# MAX2771-eval.net
KiCad netlist of a schematic drawn in Altium Designer
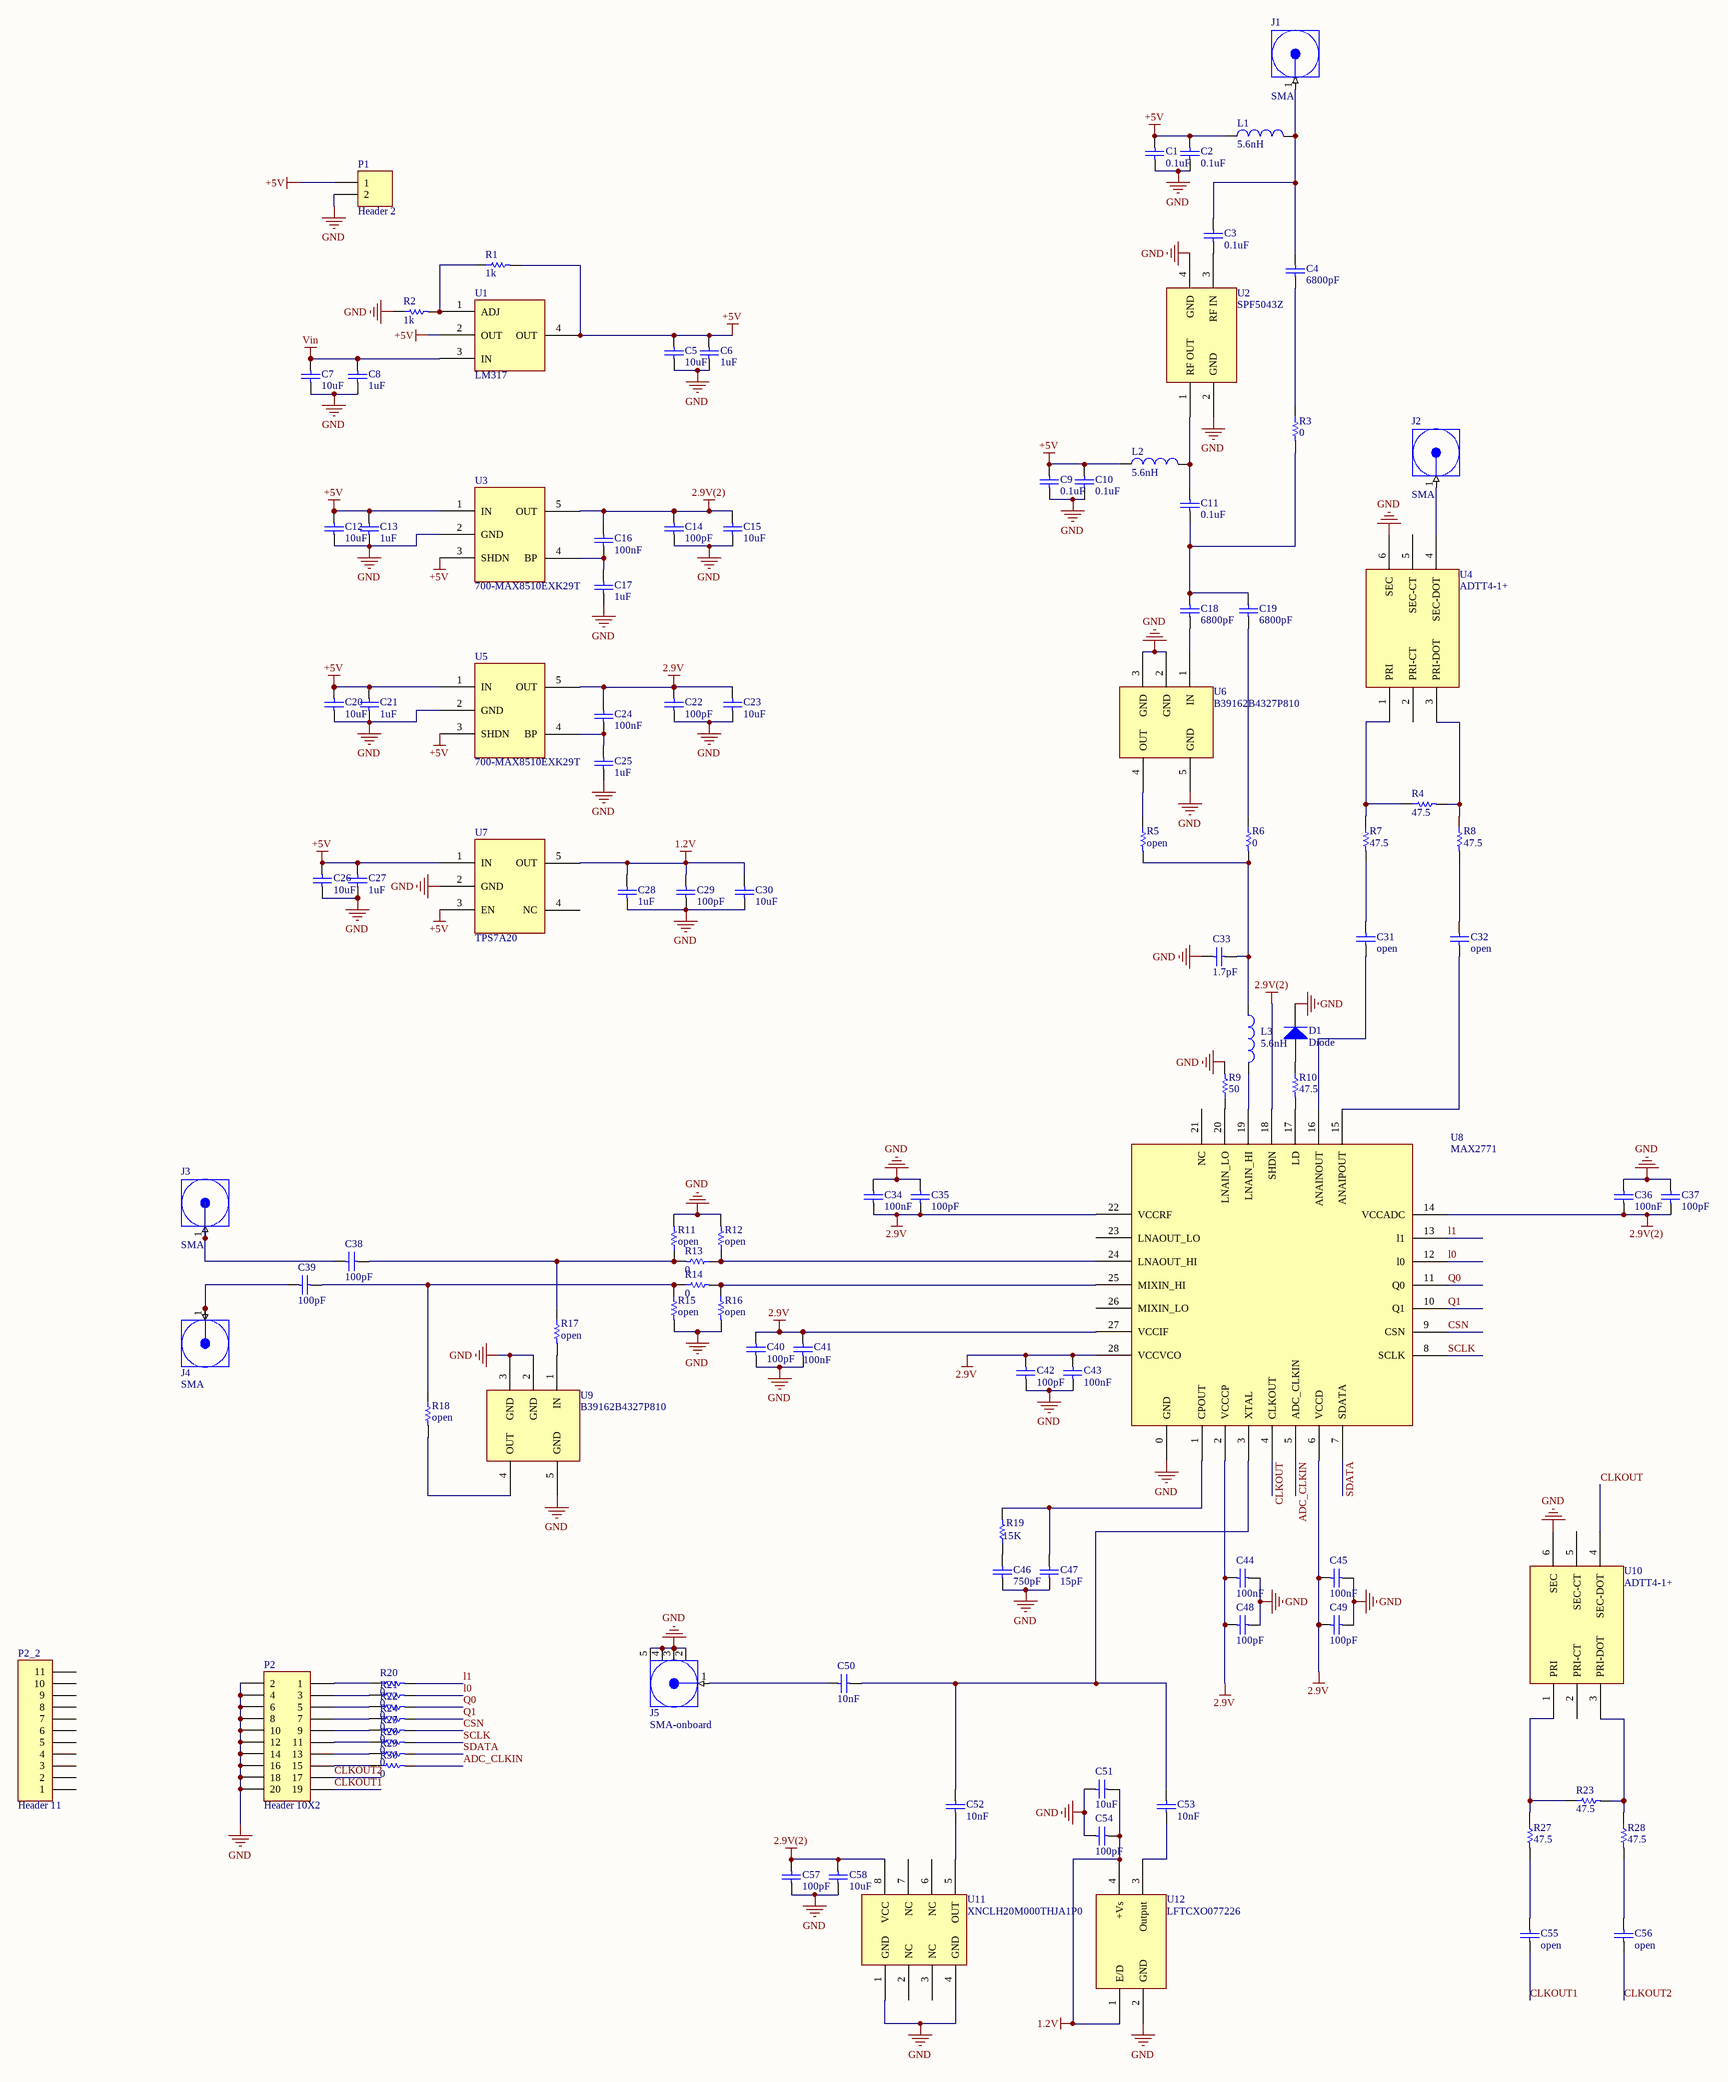
[diagram p0: MAX2771-eval.SchDoc]

(export (version "E")
  (design (tool "Eeschema 10.0.6"))
  (components
    (comp (ref "C1")
      (value "0.1uF")
      (footprint "0603")
      (description "Capacitor")
      (fields (field (name "Comment") "Cap") (field (name "PUBLISHER") "Altium Limited"))
      (libsource (lib "Miscellaneous Devices") (part "Cap"))
    )
    (comp (ref "C2")
      (value "0.1uF")
      (footprint "0603")
      (description "Capacitor")
      (fields (field (name "Comment") "Cap") (field (name "PUBLISHER") "Altium Limited"))
      (libsource (lib "Miscellaneous Devices") (part "Cap"))
    )
    (comp (ref "C3")
      (value "0.1uF")
      (footprint "0603")
      (description "Capacitor")
      (fields (field (name "Comment") "Cap") (field (name "PUBLISHER") "Altium Limited"))
      (libsource (lib "Miscellaneous Devices") (part "Cap"))
    )
    (comp (ref "C4")
      (value "6800pF")
      (footprint "0603")
      (description "Capacitor")
      (fields (field (name "Comment") "Cap") (field (name "PUBLISHER") "Altium Limited"))
      (libsource (lib "Miscellaneous Devices") (part "Cap"))
    )
    (comp (ref "C5")
      (value "10uF")
      (footprint "0603")
      (description "Capacitor")
      (fields (field (name "Comment") "Cap") (field (name "PUBLISHER") "Altium Limited"))
      (libsource (lib "Miscellaneous Devices") (part "Cap"))
    )
    (comp (ref "C6")
      (value "1uF")
      (footprint "0603")
      (description "Capacitor")
      (fields (field (name "Comment") "Cap") (field (name "PUBLISHER") "Altium Limited"))
      (libsource (lib "Miscellaneous Devices") (part "Cap"))
    )
    (comp (ref "C7")
      (value "10uF")
      (footprint "0603")
      (description "Capacitor")
      (fields (field (name "Comment") "Cap") (field (name "PUBLISHER") "Altium Limited"))
      (libsource (lib "Miscellaneous Devices") (part "Cap"))
    )
    (comp (ref "C8")
      (value "1uF")
      (footprint "0603")
      (description "Capacitor")
      (fields (field (name "Comment") "Cap") (field (name "PUBLISHER") "Altium Limited"))
      (libsource (lib "Miscellaneous Devices") (part "Cap"))
    )
    (comp (ref "C9")
      (value "0.1uF")
      (footprint "0603")
      (description "Capacitor")
      (fields (field (name "Comment") "Cap") (field (name "PUBLISHER") "Altium Limited"))
      (libsource (lib "Miscellaneous Devices") (part "Cap"))
    )
    (comp (ref "C10")
      (value "0.1uF")
      (footprint "0603")
      (description "Capacitor")
      (fields (field (name "Comment") "Cap") (field (name "PUBLISHER") "Altium Limited"))
      (libsource (lib "Miscellaneous Devices") (part "Cap"))
    )
    (comp (ref "C11")
      (value "0.1uF")
      (footprint "0603")
      (description "Capacitor")
      (fields (field (name "Comment") "Cap") (field (name "PUBLISHER") "Altium Limited"))
      (libsource (lib "Miscellaneous Devices") (part "Cap"))
    )
    (comp (ref "C12")
      (value "10uF")
      (footprint "0603")
      (description "Capacitor")
      (fields (field (name "Comment") "Cap") (field (name "PUBLISHER") "Altium Limited"))
      (libsource (lib "Miscellaneous Devices") (part "Cap"))
    )
    (comp (ref "C13")
      (value "1uF")
      (footprint "0603")
      (description "Capacitor")
      (fields (field (name "Comment") "Cap") (field (name "PUBLISHER") "Altium Limited"))
      (libsource (lib "Miscellaneous Devices") (part "Cap"))
    )
    (comp (ref "C14")
      (value "100pF")
      (footprint "0603")
      (description "Capacitor")
      (fields (field (name "Comment") "Cap") (field (name "PUBLISHER") "Altium Limited"))
      (libsource (lib "Miscellaneous Devices") (part "Cap"))
    )
    (comp (ref "C15")
      (value "10uF")
      (footprint "0603")
      (description "Capacitor")
      (fields (field (name "Comment") "Cap") (field (name "PUBLISHER") "Altium Limited"))
      (libsource (lib "Miscellaneous Devices") (part "Cap"))
    )
    (comp (ref "C16")
      (value "100nF")
      (footprint "0603")
      (description "Capacitor")
      (fields (field (name "Comment") "Cap") (field (name "PUBLISHER") "Altium Limited"))
      (libsource (lib "Miscellaneous Devices") (part "Cap"))
    )
    (comp (ref "C17")
      (value "1uF")
      (footprint "0603")
      (description "Capacitor")
      (fields (field (name "Comment") "Cap") (field (name "PUBLISHER") "Altium Limited"))
      (libsource (lib "Miscellaneous Devices") (part "Cap"))
    )
    (comp (ref "C18")
      (value "6800pF")
      (footprint "0603")
      (description "Capacitor")
      (fields (field (name "Comment") "Cap") (field (name "PUBLISHER") "Altium Limited"))
      (libsource (lib "Miscellaneous Devices") (part "Cap"))
    )
    (comp (ref "C19")
      (value "6800pF")
      (footprint "0603")
      (description "Capacitor")
      (fields (field (name "Comment") "Cap") (field (name "PUBLISHER") "Altium Limited"))
      (libsource (lib "Miscellaneous Devices") (part "Cap"))
    )
    (comp (ref "C20")
      (value "10uF")
      (footprint "0603")
      (description "Capacitor")
      (fields (field (name "Comment") "Cap") (field (name "PUBLISHER") "Altium Limited"))
      (libsource (lib "Miscellaneous Devices") (part "Cap"))
    )
    (comp (ref "C21")
      (value "1uF")
      (footprint "0603")
      (description "Capacitor")
      (fields (field (name "Comment") "Cap") (field (name "PUBLISHER") "Altium Limited"))
      (libsource (lib "Miscellaneous Devices") (part "Cap"))
    )
    (comp (ref "C22")
      (value "100pF")
      (footprint "0603")
      (description "Capacitor")
      (fields (field (name "Comment") "Cap") (field (name "PUBLISHER") "Altium Limited"))
      (libsource (lib "Miscellaneous Devices") (part "Cap"))
    )
    (comp (ref "C23")
      (value "10uF")
      (footprint "0603")
      (description "Capacitor")
      (fields (field (name "Comment") "Cap") (field (name "PUBLISHER") "Altium Limited"))
      (libsource (lib "Miscellaneous Devices") (part "Cap"))
    )
    (comp (ref "C24")
      (value "100nF")
      (footprint "0603")
      (description "Capacitor")
      (fields (field (name "Comment") "Cap") (field (name "PUBLISHER") "Altium Limited"))
      (libsource (lib "Miscellaneous Devices") (part "Cap"))
    )
    (comp (ref "C25")
      (value "1uF")
      (footprint "0603")
      (description "Capacitor")
      (fields (field (name "Comment") "Cap") (field (name "PUBLISHER") "Altium Limited"))
      (libsource (lib "Miscellaneous Devices") (part "Cap"))
    )
    (comp (ref "C26")
      (value "10uF")
      (footprint "0603")
      (description "Capacitor")
      (fields (field (name "Comment") "Cap") (field (name "PUBLISHER") "Altium Limited"))
      (libsource (lib "Miscellaneous Devices") (part "Cap"))
    )
    (comp (ref "C27")
      (value "1uF")
      (footprint "0603")
      (description "Capacitor")
      (fields (field (name "Comment") "Cap") (field (name "PUBLISHER") "Altium Limited"))
      (libsource (lib "Miscellaneous Devices") (part "Cap"))
    )
    (comp (ref "C28")
      (value "1uF")
      (footprint "0603")
      (description "Capacitor")
      (fields (field (name "Comment") "Cap") (field (name "PUBLISHER") "Altium Limited"))
      (libsource (lib "Miscellaneous Devices") (part "Cap"))
    )
    (comp (ref "C29")
      (value "100pF")
      (footprint "0603")
      (description "Capacitor")
      (fields (field (name "Comment") "Cap") (field (name "PUBLISHER") "Altium Limited"))
      (libsource (lib "Miscellaneous Devices") (part "Cap"))
    )
    (comp (ref "C30")
      (value "10uF")
      (footprint "0603")
      (description "Capacitor")
      (fields (field (name "Comment") "Cap") (field (name "PUBLISHER") "Altium Limited"))
      (libsource (lib "Miscellaneous Devices") (part "Cap"))
    )
    (comp (ref "C31")
      (value "open")
      (footprint "0603")
      (description "Capacitor")
      (fields (field (name "Comment") "Cap") (field (name "PUBLISHER") "Altium Limited"))
      (libsource (lib "Miscellaneous Devices") (part "Cap"))
    )
    (comp (ref "C32")
      (value "open")
      (footprint "0603")
      (description "Capacitor")
      (fields (field (name "Comment") "Cap") (field (name "PUBLISHER") "Altium Limited"))
      (libsource (lib "Miscellaneous Devices") (part "Cap"))
    )
    (comp (ref "C33")
      (value "1.7pF")
      (footprint "0603")
      (description "Capacitor")
      (fields (field (name "Comment") "Cap") (field (name "PUBLISHER") "Altium Limited"))
      (libsource (lib "Miscellaneous Devices") (part "Cap"))
    )
    (comp (ref "C34")
      (value "100nF")
      (footprint "0603")
      (description "Capacitor")
      (fields (field (name "Comment") "Cap") (field (name "PUBLISHER") "Altium Limited"))
      (libsource (lib "Miscellaneous Devices") (part "Cap"))
    )
    (comp (ref "C35")
      (value "100pF")
      (footprint "0603")
      (description "Capacitor")
      (fields (field (name "Comment") "Cap") (field (name "PUBLISHER") "Altium Limited"))
      (libsource (lib "Miscellaneous Devices") (part "Cap"))
    )
    (comp (ref "C36")
      (value "100nF")
      (footprint "0603")
      (description "Capacitor")
      (fields (field (name "Comment") "Cap") (field (name "PUBLISHER") "Altium Limited"))
      (libsource (lib "Miscellaneous Devices") (part "Cap"))
    )
    (comp (ref "C37")
      (value "100pF")
      (footprint "0603")
      (description "Capacitor")
      (fields (field (name "Comment") "Cap") (field (name "PUBLISHER") "Altium Limited"))
      (libsource (lib "Miscellaneous Devices") (part "Cap"))
    )
    (comp (ref "C38")
      (value "100pF")
      (footprint "0603")
      (description "Capacitor")
      (fields (field (name "Comment") "Cap") (field (name "PUBLISHER") "Altium Limited"))
      (libsource (lib "Miscellaneous Devices") (part "Cap"))
    )
    (comp (ref "C39")
      (value "100pF")
      (footprint "0603")
      (description "Capacitor")
      (fields (field (name "Comment") "Cap") (field (name "PUBLISHER") "Altium Limited"))
      (libsource (lib "Miscellaneous Devices") (part "Cap"))
    )
    (comp (ref "C40")
      (value "100pF")
      (footprint "0603")
      (description "Capacitor")
      (fields (field (name "Comment") "Cap") (field (name "PUBLISHER") "Altium Limited"))
      (libsource (lib "Miscellaneous Devices") (part "Cap"))
    )
    (comp (ref "C41")
      (value "100nF")
      (footprint "0603")
      (description "Capacitor")
      (fields (field (name "Comment") "Cap") (field (name "PUBLISHER") "Altium Limited"))
      (libsource (lib "Miscellaneous Devices") (part "Cap"))
    )
    (comp (ref "C42")
      (value "100pF")
      (footprint "0603")
      (description "Capacitor")
      (fields (field (name "Comment") "Cap") (field (name "PUBLISHER") "Altium Limited"))
      (libsource (lib "Miscellaneous Devices") (part "Cap"))
    )
    (comp (ref "C43")
      (value "100nF")
      (footprint "0603")
      (description "Capacitor")
      (fields (field (name "Comment") "Cap") (field (name "PUBLISHER") "Altium Limited"))
      (libsource (lib "Miscellaneous Devices") (part "Cap"))
    )
    (comp (ref "C44")
      (value "100nF")
      (footprint "0603")
      (description "Capacitor")
      (fields (field (name "Comment") "Cap") (field (name "PUBLISHER") "Altium Limited"))
      (libsource (lib "Miscellaneous Devices") (part "Cap"))
    )
    (comp (ref "C45")
      (value "100nF")
      (footprint "0603")
      (description "Capacitor")
      (fields (field (name "Comment") "Cap") (field (name "PUBLISHER") "Altium Limited"))
      (libsource (lib "Miscellaneous Devices") (part "Cap"))
    )
    (comp (ref "C46")
      (value "750pF")
      (footprint "0603")
      (description "Capacitor")
      (fields (field (name "Comment") "Cap") (field (name "PUBLISHER") "Altium Limited"))
      (libsource (lib "Miscellaneous Devices") (part "Cap"))
    )
    (comp (ref "C47")
      (value "15pF")
      (footprint "0603")
      (description "Capacitor")
      (fields (field (name "Comment") "Cap") (field (name "PUBLISHER") "Altium Limited"))
      (libsource (lib "Miscellaneous Devices") (part "Cap"))
    )
    (comp (ref "C48")
      (value "100pF")
      (footprint "0603")
      (description "Capacitor")
      (fields (field (name "Comment") "Cap") (field (name "PUBLISHER") "Altium Limited"))
      (libsource (lib "Miscellaneous Devices") (part "Cap"))
    )
    (comp (ref "C49")
      (value "100pF")
      (footprint "0603")
      (description "Capacitor")
      (fields (field (name "Comment") "Cap") (field (name "PUBLISHER") "Altium Limited"))
      (libsource (lib "Miscellaneous Devices") (part "Cap"))
    )
    (comp (ref "C50")
      (value "10nF")
      (footprint "0603")
      (description "Capacitor")
      (fields (field (name "Comment") "Cap") (field (name "PUBLISHER") "Altium Limited"))
      (libsource (lib "Miscellaneous Devices") (part "Cap"))
    )
    (comp (ref "C51")
      (value "10uF")
      (footprint "0603")
      (description "Capacitor")
      (fields (field (name "Comment") "Cap") (field (name "PUBLISHER") "Altium Limited"))
      (libsource (lib "Miscellaneous Devices") (part "Cap"))
    )
    (comp (ref "C52")
      (value "10nF")
      (footprint "0603")
      (description "Capacitor")
      (fields (field (name "Comment") "Cap") (field (name "PUBLISHER") "Altium Limited"))
      (libsource (lib "Miscellaneous Devices") (part "Cap"))
    )
    (comp (ref "C53")
      (value "10nF")
      (footprint "0603")
      (description "Capacitor")
      (fields (field (name "Comment") "Cap") (field (name "PUBLISHER") "Altium Limited"))
      (libsource (lib "Miscellaneous Devices") (part "Cap"))
    )
    (comp (ref "C54")
      (value "100pF")
      (footprint "0603")
      (description "Capacitor")
      (fields (field (name "Comment") "Cap") (field (name "PUBLISHER") "Altium Limited"))
      (libsource (lib "Miscellaneous Devices") (part "Cap"))
    )
    (comp (ref "C55")
      (value "open")
      (footprint "0603")
      (description "Capacitor")
      (fields (field (name "Comment") "Cap") (field (name "PUBLISHER") "Altium Limited"))
      (libsource (lib "Miscellaneous Devices") (part "Cap"))
    )
    (comp (ref "C56")
      (value "open")
      (footprint "0603")
      (description "Capacitor")
      (fields (field (name "Comment") "Cap") (field (name "PUBLISHER") "Altium Limited"))
      (libsource (lib "Miscellaneous Devices") (part "Cap"))
    )
    (comp (ref "C57")
      (value "100pF")
      (footprint "0603")
      (description "Capacitor")
      (fields (field (name "Comment") "Cap") (field (name "PUBLISHER") "Altium Limited"))
      (libsource (lib "Miscellaneous Devices") (part "Cap"))
    )
    (comp (ref "C58")
      (value "10uF")
      (footprint "0603")
      (description "Capacitor")
      (fields (field (name "Comment") "Cap") (field (name "PUBLISHER") "Altium Limited"))
      (libsource (lib "Miscellaneous Devices") (part "Cap"))
    )
    (comp (ref "D1")
      (value "Diode")
      (footprint "GPS-lib:0603")
      (description "Default Diode")
      (fields (field (name "PUBLISHER") "Altium Limited"))
      (libsource (lib "Miscellaneous Devices") (part "Diode"))
    )
    (comp (ref "J1") (value "SMA") (footprint "GPS-lib:SMA") (libsource (lib "GPS-lib") (part "SMA")))
    (comp (ref "J2") (value "SMA") (footprint "GPS-lib:SMA") (libsource (lib "GPS-lib") (part "SMA")))
    (comp (ref "J3") (value "SMA") (footprint "GPS-lib:SMA") (libsource (lib "GPS-lib") (part "SMA")))
    (comp (ref "J4") (value "SMA") (footprint "GPS-lib:SMA") (libsource (lib "GPS-lib") (part "SMA")))
    (comp (ref "J5")
      (value "SMA-onboard")
      (footprint "GPS-lib:SMA-onboard")
      (libsource (lib "GPS-lib") (part "SMA-onboard"))
    )
    (comp (ref "L1")
      (value "5.6nH")
      (footprint "GPS-lib:0603")
      (description "Inductor")
      (fields (field (name "PUBLISHER") "Altium Limited"))
      (libsource (lib "Miscellaneous Devices") (part "Inductor"))
    )
    (comp (ref "L2")
      (value "5.6nH")
      (footprint "GPS-lib:0603")
      (description "Inductor")
      (fields (field (name "PUBLISHER") "Altium Limited"))
      (libsource (lib "Miscellaneous Devices") (part "Inductor"))
    )
    (comp (ref "L3")
      (value "5.6nH")
      (footprint "0603")
      (description "Inductor")
      (fields (field (name "PUBLISHER") "Altium Limited"))
      (libsource (lib "Miscellaneous Devices") (part "Inductor"))
    )
    (comp (ref "P1")
      (value "Header 2")
      (footprint "HDR1X2")
      (description "Header, 2-Pin")
      (fields (field (name "PUBLISHER") "Altium Limited"))
      (libsource (lib "Miscellaneous Connectors") (part "Header 2"))
    )
    (comp (ref "P2")
      (value "Header 10X2")
      (footprint "HDR2X10")
      (description "Header, 10-Pin, Dual row")
      (fields (field (name "PUBLISHER") "Altium Limited"))
      (libsource (lib "Miscellaneous Connectors") (part "Header 10X2"))
    )
    (comp (ref "P2_2")
      (value "Header 11")
      (footprint "HDR1X11")
      (description "Header, 11-Pin")
      (fields (field (name "PUBLISHER") "Altium Limited"))
      (libsource (lib "Miscellaneous Connectors") (part "Header 11"))
    )
    (comp (ref "R1")
      (value "1k")
      (footprint "0603")
      (description "Resistor")
      (fields (field (name "Comment") "Res1") (field (name "PUBLISHER") "Altium Limited"))
      (libsource (lib "Miscellaneous Devices") (part "Res1"))
    )
    (comp (ref "R2")
      (value "1k")
      (footprint "0603")
      (description "Resistor")
      (fields (field (name "Comment") "Res1") (field (name "PUBLISHER") "Altium Limited"))
      (libsource (lib "Miscellaneous Devices") (part "Res1"))
    )
    (comp (ref "R3")
      (value "0")
      (footprint "0603")
      (description "Resistor")
      (fields (field (name "Comment") "Res1") (field (name "PUBLISHER") "Altium Limited"))
      (libsource (lib "Miscellaneous Devices") (part "Res1"))
    )
    (comp (ref "R4")
      (value "47.5")
      (footprint "0603")
      (description "Resistor")
      (fields (field (name "Comment") "Res1") (field (name "PUBLISHER") "Altium Limited"))
      (libsource (lib "Miscellaneous Devices") (part "Res1"))
    )
    (comp (ref "R5")
      (value "open")
      (footprint "0603")
      (description "Resistor")
      (fields (field (name "Comment") "Res1") (field (name "PUBLISHER") "Altium Limited"))
      (libsource (lib "Miscellaneous Devices") (part "Res1"))
    )
    (comp (ref "R6")
      (value "0")
      (footprint "0603")
      (description "Resistor")
      (fields (field (name "Comment") "Res1") (field (name "PUBLISHER") "Altium Limited"))
      (libsource (lib "Miscellaneous Devices") (part "Res1"))
    )
    (comp (ref "R7")
      (value "47.5")
      (footprint "0603")
      (description "Resistor")
      (fields (field (name "Comment") "Res1") (field (name "PUBLISHER") "Altium Limited"))
      (libsource (lib "Miscellaneous Devices") (part "Res1"))
    )
    (comp (ref "R8")
      (value "47.5")
      (footprint "0603")
      (description "Resistor")
      (fields (field (name "Comment") "Res1") (field (name "PUBLISHER") "Altium Limited"))
      (libsource (lib "Miscellaneous Devices") (part "Res1"))
    )
    (comp (ref "R9")
      (value "50")
      (footprint "0603")
      (description "Resistor")
      (fields (field (name "Comment") "Res1") (field (name "PUBLISHER") "Altium Limited"))
      (libsource (lib "Miscellaneous Devices") (part "Res1"))
    )
    (comp (ref "R10")
      (value "47.5")
      (footprint "0603")
      (description "Resistor")
      (fields (field (name "Comment") "Res1") (field (name "PUBLISHER") "Altium Limited"))
      (libsource (lib "Miscellaneous Devices") (part "Res1"))
    )
    (comp (ref "R11")
      (value "open")
      (footprint "0603")
      (description "Resistor")
      (fields (field (name "Comment") "Res1") (field (name "PUBLISHER") "Altium Limited"))
      (libsource (lib "Miscellaneous Devices") (part "Res1"))
    )
    (comp (ref "R12")
      (value "open")
      (footprint "0603")
      (description "Resistor")
      (fields (field (name "Comment") "Res1") (field (name "PUBLISHER") "Altium Limited"))
      (libsource (lib "Miscellaneous Devices") (part "Res1"))
    )
    (comp (ref "R13")
      (value "0")
      (footprint "GPS-lib:0603")
      (description "Resistor")
      (fields (field (name "Comment") "Res1") (field (name "PUBLISHER") "Altium Limited"))
      (libsource (lib "Miscellaneous Devices") (part "Res1"))
    )
    (comp (ref "R14")
      (value "0")
      (footprint "GPS-lib:0603")
      (description "Resistor")
      (fields (field (name "Comment") "Res1") (field (name "PUBLISHER") "Altium Limited"))
      (libsource (lib "Miscellaneous Devices") (part "Res1"))
    )
    (comp (ref "R15")
      (value "open")
      (footprint "0603")
      (description "Resistor")
      (fields (field (name "Comment") "Res1") (field (name "PUBLISHER") "Altium Limited"))
      (libsource (lib "Miscellaneous Devices") (part "Res1"))
    )
    (comp (ref "R16")
      (value "open")
      (footprint "0603")
      (description "Resistor")
      (fields (field (name "Comment") "Res1") (field (name "PUBLISHER") "Altium Limited"))
      (libsource (lib "Miscellaneous Devices") (part "Res1"))
    )
    (comp (ref "R17")
      (value "open")
      (footprint "0603")
      (description "Resistor")
      (fields (field (name "Comment") "Res1") (field (name "PUBLISHER") "Altium Limited"))
      (libsource (lib "Miscellaneous Devices") (part "Res1"))
    )
    (comp (ref "R18")
      (value "open")
      (footprint "0603")
      (description "Resistor")
      (fields (field (name "Comment") "Res1") (field (name "PUBLISHER") "Altium Limited"))
      (libsource (lib "Miscellaneous Devices") (part "Res1"))
    )
    (comp (ref "R19")
      (value "15K")
      (footprint "0603")
      (description "Resistor")
      (fields (field (name "Comment") "Res1") (field (name "PUBLISHER") "Altium Limited"))
      (libsource (lib "Miscellaneous Devices") (part "Res1"))
    )
    (comp (ref "R20")
      (value "0")
      (footprint "GPS-lib:0402")
      (description "Resistor")
      (fields (field (name "Comment") "Res1") (field (name "PUBLISHER") "Altium Limited"))
      (libsource (lib "Miscellaneous Devices") (part "Res1"))
    )
    (comp (ref "R21")
      (value "0")
      (footprint "GPS-lib:0402")
      (description "Resistor")
      (fields (field (name "Comment") "Res1") (field (name "PUBLISHER") "Altium Limited"))
      (libsource (lib "Miscellaneous Devices") (part "Res1"))
    )
    (comp (ref "R22")
      (value "0")
      (footprint "GPS-lib:0402")
      (description "Resistor")
      (fields (field (name "Comment") "Res1") (field (name "PUBLISHER") "Altium Limited"))
      (libsource (lib "Miscellaneous Devices") (part "Res1"))
    )
    (comp (ref "R23")
      (value "47.5")
      (footprint "0603")
      (description "Resistor")
      (fields (field (name "Comment") "Res1") (field (name "PUBLISHER") "Altium Limited"))
      (libsource (lib "Miscellaneous Devices") (part "Res1"))
    )
    (comp (ref "R24")
      (value "0")
      (footprint "GPS-lib:0402")
      (description "Resistor")
      (fields (field (name "Comment") "Res1") (field (name "PUBLISHER") "Altium Limited"))
      (libsource (lib "Miscellaneous Devices") (part "Res1"))
    )
    (comp (ref "R25")
      (value "0")
      (footprint "GPS-lib:0402")
      (description "Resistor")
      (fields (field (name "Comment") "Res1") (field (name "PUBLISHER") "Altium Limited"))
      (libsource (lib "Miscellaneous Devices") (part "Res1"))
    )
    (comp (ref "R26")
      (value "0")
      (footprint "GPS-lib:0402")
      (description "Resistor")
      (fields (field (name "Comment") "Res1") (field (name "PUBLISHER") "Altium Limited"))
      (libsource (lib "Miscellaneous Devices") (part "Res1"))
    )
    (comp (ref "R27")
      (value "47.5")
      (footprint "0603")
      (description "Resistor")
      (fields (field (name "Comment") "Res1") (field (name "PUBLISHER") "Altium Limited"))
      (libsource (lib "Miscellaneous Devices") (part "Res1"))
    )
    (comp (ref "R28")
      (value "47.5")
      (footprint "0603")
      (description "Resistor")
      (fields (field (name "Comment") "Res1") (field (name "PUBLISHER") "Altium Limited"))
      (libsource (lib "Miscellaneous Devices") (part "Res1"))
    )
    (comp (ref "R29")
      (value "0")
      (footprint "GPS-lib:0402")
      (description "Resistor")
      (fields (field (name "Comment") "Res1") (field (name "PUBLISHER") "Altium Limited"))
      (libsource (lib "Miscellaneous Devices") (part "Res1"))
    )
    (comp (ref "R30")
      (value "0")
      (footprint "GPS-lib:0402")
      (description "Resistor")
      (fields (field (name "Comment") "Res1") (field (name "PUBLISHER") "Altium Limited"))
      (libsource (lib "Miscellaneous Devices") (part "Res1"))
    )
    (comp (ref "U1") (value "LM317") (footprint "GPS-lib:SOT223") (libsource (lib "GPS-lib") (part "LM317")))
    (comp (ref "U2")
      (value "SPF5043Z")
      (footprint "GPS-lib:SPF5043Z")
      (libsource (lib "GPS-lib") (part "SPF5043Z"))
    )
    (comp (ref "U3")
      (value "700-MAX8510EXK29T")
      (footprint "SC70")
      (libsource (lib "GPS-lib") (part "700-MAX8510EXK29T"))
    )
    (comp (ref "U4")
      (value "ADTT4-1+")
      (footprint "GPS-lib:ADTT4-1+")
      (libsource (lib "GPS-lib") (part "ADTT4-1+"))
    )
    (comp (ref "U5")
      (value "700-MAX8510EXK29T")
      (footprint "SC70")
      (libsource (lib "GPS-lib") (part "700-MAX8510EXK29T"))
    )
    (comp (ref "U6")
      (value "B39162B4327P810")
      (footprint "GPS-lib:B39162B4327P810")
      (libsource (lib "GPS-lib") (part "B39162B4327P810"))
    )
    (comp (ref "U7")
      (value "TPS7A20")
      (footprint "GPS-lib:SOT23-5")
      (libsource (lib "GPS-lib") (part "TPS7A20"))
    )
    (comp (ref "U8")
      (value "MAX2771")
      (footprint "GPS-lib:MAX2771")
      (description "Multiband Universal GNSS Receiver")
      (libsource (lib "GPS-lib") (part "MAX2771"))
    )
    (comp (ref "U9")
      (value "B39162B4327P810")
      (footprint "GPS-lib:B39162B4327P810")
      (libsource (lib "GPS-lib") (part "B39162B4327P810"))
    )
    (comp (ref "U10")
      (value "ADTT4-1+")
      (footprint "GPS-lib:ADTT4-1+")
      (libsource (lib "GPS-lib") (part "ADTT4-1+"))
    )
    (comp (ref "U11")
      (value "XNCLH20M000THJA1P0")
      (footprint "XNCLH20M000THJA1P0")
      (libsource (lib "GPS-lib") (part "XNCLH20M000THJA1P0"))
    )
    (comp (ref "U12")
      (value "LFTCXO077226")
      (footprint "GPS-lib:IQXT-225")
      (libsource (lib "GPS-lib") (part "LFTCXO077226"))
    )
  )
  (nets
    (net (code "1") (name "+5V") (class "Default")
      (node (ref "C1") (pin "1") (pinfunction "1_1") (pintype "passive"))
      (node (ref "C10") (pin "1") (pinfunction "1_1") (pintype "passive"))
      (node (ref "C12") (pin "2") (pinfunction "2_2") (pintype "passive"))
      (node (ref "C13") (pin "2") (pinfunction "2_2") (pintype "passive"))
      (node (ref "C2") (pin "1") (pinfunction "1_1") (pintype "passive"))
      (node (ref "C20") (pin "2") (pinfunction "2_2") (pintype "passive"))
      (node (ref "C21") (pin "2") (pinfunction "2_2") (pintype "passive"))
      (node (ref "C26") (pin "2") (pinfunction "2_2") (pintype "passive"))
      (node (ref "C27") (pin "2") (pinfunction "2_2") (pintype "passive"))
      (node (ref "C5") (pin "2") (pinfunction "2_2") (pintype "passive"))
      (node (ref "C6") (pin "2") (pinfunction "2_2") (pintype "passive"))
      (node (ref "C9") (pin "1") (pinfunction "1_1") (pintype "passive"))
      (node (ref "L1") (pin "1") (pinfunction "1_1") (pintype "passive"))
      (node (ref "L2") (pin "1") (pinfunction "1_1") (pintype "passive"))
      (node (ref "P1") (pin "1") (pinfunction "1_1") (pintype "passive"))
      (node (ref "R1") (pin "2") (pinfunction "2_2") (pintype "passive"))
      (node (ref "U1") (pin "2") (pinfunction "OUT_2") (pintype "passive"))
      (node (ref "U1") (pin "4") (pinfunction "OUT_4") (pintype "passive"))
      (node (ref "U3") (pin "1") (pinfunction "IN_1") (pintype "passive"))
      (node (ref "U3") (pin "3") (pinfunction "SHDN_3") (pintype "passive"))
      (node (ref "U5") (pin "1") (pinfunction "IN_1") (pintype "passive"))
      (node (ref "U5") (pin "3") (pinfunction "SHDN_3") (pintype "passive"))
      (node (ref "U7") (pin "1") (pinfunction "IN_1") (pintype "passive"))
      (node (ref "U7") (pin "3") (pinfunction "EN_3") (pintype "passive"))
    )
    (net (code "2") (name "/ADC_CLKIN") (class "Default")
      (node (ref "R30") (pin "2") (pinfunction "2_2") (pintype "passive"))
      (node (ref "U8") (pin "5") (pinfunction "ADC_CLKIN_5") (pintype "passive"))
    )
    (net (code "3") (name "/CLKOUT") (class "Default")
      (node (ref "U10") (pin "4") (pinfunction "SEC-DOT_4") (pintype "passive"))
      (node (ref "U8") (pin "4") (pinfunction "CLKOUT_4") (pintype "passive"))
    )
    (net (code "4") (name "/CLKOUT1") (class "Default")
      (node (ref "C55") (pin "1") (pinfunction "1_1") (pintype "passive"))
      (node (ref "P2") (pin "19") (pinfunction "19_19") (pintype "passive"))
    )
    (net (code "5") (name "/CLKOUT2") (class "Default")
      (node (ref "C56") (pin "1") (pinfunction "1_1") (pintype "passive"))
      (node (ref "P2") (pin "17") (pinfunction "17_17") (pintype "passive"))
    )
    (net (code "6") (name "/CSN") (class "Default")
      (node (ref "R25") (pin "2") (pinfunction "2_2") (pintype "passive"))
      (node (ref "U8") (pin "9") (pinfunction "CSN_9") (pintype "passive"))
    )
    (net (code "7") (name "/Q0") (class "Default")
      (node (ref "R22") (pin "2") (pinfunction "2_2") (pintype "passive"))
      (node (ref "U8") (pin "11") (pinfunction "Q0_11") (pintype "passive"))
    )
    (net (code "8") (name "/Q1") (class "Default")
      (node (ref "R24") (pin "2") (pinfunction "2_2") (pintype "passive"))
      (node (ref "U8") (pin "10") (pinfunction "Q1_10") (pintype "passive"))
    )
    (net (code "9") (name "/SCLK") (class "Default")
      (node (ref "R26") (pin "2") (pinfunction "2_2") (pintype "passive"))
      (node (ref "U8") (pin "8") (pinfunction "SCLK_8") (pintype "passive"))
    )
    (net (code "10") (name "/SDATA") (class "Default")
      (node (ref "R29") (pin "2") (pinfunction "2_2") (pintype "passive"))
      (node (ref "U8") (pin "7") (pinfunction "SDATA_7") (pintype "passive"))
    )
    (net (code "11") (name "/l0") (class "Default")
      (node (ref "R21") (pin "2") (pinfunction "2_2") (pintype "passive"))
      (node (ref "U8") (pin "12") (pinfunction "l0_12") (pintype "passive"))
    )
    (net (code "12") (name "/l1") (class "Default")
      (node (ref "R20") (pin "2") (pinfunction "2_2") (pintype "passive"))
      (node (ref "U8") (pin "13") (pinfunction "l1_13") (pintype "passive"))
    )
    (net (code "13") (name "1.2V") (class "Default")
      (node (ref "C28") (pin "2") (pinfunction "2_2") (pintype "passive"))
      (node (ref "C29") (pin "2") (pinfunction "2_2") (pintype "passive"))
      (node (ref "C30") (pin "2") (pinfunction "2_2") (pintype "passive"))
      (node (ref "C51") (pin "2") (pinfunction "2_2") (pintype "passive"))
      (node (ref "C54") (pin "2") (pinfunction "2_2") (pintype "passive"))
      (node (ref "U12") (pin "1") (pinfunction "E/D_1") (pintype "passive"))
      (node (ref "U12") (pin "4") (pinfunction "+Vs_4") (pintype "passive"))
      (node (ref "U7") (pin "5") (pinfunction "OUT_5") (pintype "passive"))
    )
    (net (code "14") (name "2.9V") (class "Default")
      (node (ref "C22") (pin "2") (pinfunction "2_2") (pintype "passive"))
      (node (ref "C23") (pin "2") (pinfunction "2_2") (pintype "passive"))
      (node (ref "C24") (pin "2") (pinfunction "2_2") (pintype "passive"))
      (node (ref "C34") (pin "2") (pinfunction "2_2") (pintype "passive"))
      (node (ref "C35") (pin "2") (pinfunction "2_2") (pintype "passive"))
      (node (ref "C40") (pin "2") (pinfunction "2_2") (pintype "passive"))
      (node (ref "C41") (pin "2") (pinfunction "2_2") (pintype "passive"))
      (node (ref "C42") (pin "2") (pinfunction "2_2") (pintype "passive"))
      (node (ref "C43") (pin "2") (pinfunction "2_2") (pintype "passive"))
      (node (ref "C44") (pin "2") (pinfunction "2_2") (pintype "passive"))
      (node (ref "C45") (pin "2") (pinfunction "2_2") (pintype "passive"))
      (node (ref "C48") (pin "2") (pinfunction "2_2") (pintype "passive"))
      (node (ref "C49") (pin "2") (pinfunction "2_2") (pintype "passive"))
      (node (ref "U5") (pin "5") (pinfunction "OUT_5") (pintype "passive"))
      (node (ref "U8") (pin "2") (pinfunction "VCCCP_2") (pintype "passive"))
      (node (ref "U8") (pin "22") (pinfunction "VCCRF_22") (pintype "passive"))
      (node (ref "U8") (pin "27") (pinfunction "VCCIF_27") (pintype "passive"))
      (node (ref "U8") (pin "28") (pinfunction "VCCVCO_28") (pintype "passive"))
      (node (ref "U8") (pin "6") (pinfunction "VCCD_6") (pintype "passive"))
    )
    (net (code "15") (name "2.9V(2)") (class "Default")
      (node (ref "C14") (pin "2") (pinfunction "2_2") (pintype "passive"))
      (node (ref "C15") (pin "2") (pinfunction "2_2") (pintype "passive"))
      (node (ref "C16") (pin "2") (pinfunction "2_2") (pintype "passive"))
      (node (ref "C36") (pin "2") (pinfunction "2_2") (pintype "passive"))
      (node (ref "C37") (pin "2") (pinfunction "2_2") (pintype "passive"))
      (node (ref "C57") (pin "2") (pinfunction "2_2") (pintype "passive"))
      (node (ref "C58") (pin "2") (pinfunction "2_2") (pintype "passive"))
      (node (ref "U11") (pin "8") (pinfunction "VCC_8") (pintype "passive"))
      (node (ref "U3") (pin "5") (pinfunction "OUT_5") (pintype "passive"))
      (node (ref "U8") (pin "14") (pinfunction "VCCADC_14") (pintype "passive"))
      (node (ref "U8") (pin "18") (pinfunction "SHDN_18") (pintype "passive"))
    )
    (net (code "16") (name "GND") (class "Default")
      (node (ref "C1") (pin "2") (pinfunction "2_2") (pintype "passive"))
      (node (ref "C10") (pin "2") (pinfunction "2_2") (pintype "passive"))
      (node (ref "C12") (pin "1") (pinfunction "1_1") (pintype "passive"))
      (node (ref "C13") (pin "1") (pinfunction "1_1") (pintype "passive"))
      (node (ref "C14") (pin "1") (pinfunction "1_1") (pintype "passive"))
      (node (ref "C15") (pin "1") (pinfunction "1_1") (pintype "passive"))
      (node (ref "C17") (pin "1") (pinfunction "1_1") (pintype "passive"))
      (node (ref "C2") (pin "2") (pinfunction "2_2") (pintype "passive"))
      (node (ref "C20") (pin "1") (pinfunction "1_1") (pintype "passive"))
      (node (ref "C21") (pin "1") (pinfunction "1_1") (pintype "passive"))
      (node (ref "C22") (pin "1") (pinfunction "1_1") (pintype "passive"))
      (node (ref "C23") (pin "1") (pinfunction "1_1") (pintype "passive"))
      (node (ref "C25") (pin "1") (pinfunction "1_1") (pintype "passive"))
      (node (ref "C26") (pin "1") (pinfunction "1_1") (pintype "passive"))
      (node (ref "C27") (pin "1") (pinfunction "1_1") (pintype "passive"))
      (node (ref "C28") (pin "1") (pinfunction "1_1") (pintype "passive"))
      (node (ref "C29") (pin "1") (pinfunction "1_1") (pintype "passive"))
      (node (ref "C30") (pin "1") (pinfunction "1_1") (pintype "passive"))
      (node (ref "C33") (pin "2") (pinfunction "2_2") (pintype "passive"))
      (node (ref "C34") (pin "1") (pinfunction "1_1") (pintype "passive"))
      (node (ref "C35") (pin "1") (pinfunction "1_1") (pintype "passive"))
      (node (ref "C36") (pin "1") (pinfunction "1_1") (pintype "passive"))
      (node (ref "C37") (pin "1") (pinfunction "1_1") (pintype "passive"))
      (node (ref "C40") (pin "1") (pinfunction "1_1") (pintype "passive"))
      (node (ref "C41") (pin "1") (pinfunction "1_1") (pintype "passive"))
      (node (ref "C42") (pin "1") (pinfunction "1_1") (pintype "passive"))
      (node (ref "C43") (pin "1") (pinfunction "1_1") (pintype "passive"))
      (node (ref "C44") (pin "1") (pinfunction "1_1") (pintype "passive"))
      (node (ref "C45") (pin "1") (pinfunction "1_1") (pintype "passive"))
      (node (ref "C46") (pin "1") (pinfunction "1_1") (pintype "passive"))
      (node (ref "C47") (pin "1") (pinfunction "1_1") (pintype "passive"))
      (node (ref "C48") (pin "1") (pinfunction "1_1") (pintype "passive"))
      (node (ref "C49") (pin "1") (pinfunction "1_1") (pintype "passive"))
      (node (ref "C5") (pin "1") (pinfunction "1_1") (pintype "passive"))
      (node (ref "C51") (pin "1") (pinfunction "1_1") (pintype "passive"))
      (node (ref "C54") (pin "1") (pinfunction "1_1") (pintype "passive"))
      (node (ref "C57") (pin "1") (pinfunction "1_1") (pintype "passive"))
      (node (ref "C58") (pin "1") (pinfunction "1_1") (pintype "passive"))
      (node (ref "C6") (pin "1") (pinfunction "1_1") (pintype "passive"))
      (node (ref "C7") (pin "1") (pinfunction "1_1") (pintype "passive"))
      (node (ref "C8") (pin "1") (pinfunction "1_1") (pintype "passive"))
      (node (ref "C9") (pin "2") (pinfunction "2_2") (pintype "passive"))
      (node (ref "D1") (pin "2") (pinfunction "K_2") (pintype "passive"))
      (node (ref "J5") (pin "2") (pinfunction "GND_2") (pintype "power_in"))
      (node (ref "J5") (pin "3") (pinfunction "GND_3") (pintype "power_in"))
      (node (ref "J5") (pin "4") (pinfunction "GND_4") (pintype "power_in"))
      (node (ref "J5") (pin "5") (pinfunction "GND_5") (pintype "power_in"))
      (node (ref "P1") (pin "2") (pinfunction "2_2") (pintype "passive"))
      (node (ref "P2") (pin "10") (pinfunction "10_10") (pintype "passive"))
      (node (ref "P2") (pin "12") (pinfunction "12_12") (pintype "passive"))
      (node (ref "P2") (pin "14") (pinfunction "14_14") (pintype "passive"))
      (node (ref "P2") (pin "16") (pinfunction "16_16") (pintype "passive"))
      (node (ref "P2") (pin "18") (pinfunction "18_18") (pintype "passive"))
      (node (ref "P2") (pin "2") (pinfunction "2_2") (pintype "passive"))
      (node (ref "P2") (pin "20") (pinfunction "20_20") (pintype "passive"))
      (node (ref "P2") (pin "4") (pinfunction "4_4") (pintype "passive"))
      (node (ref "P2") (pin "6") (pinfunction "6_6") (pintype "passive"))
      (node (ref "P2") (pin "8") (pinfunction "8_8") (pintype "passive"))
      (node (ref "R11") (pin "2") (pinfunction "2_2") (pintype "passive"))
      (node (ref "R12") (pin "2") (pinfunction "2_2") (pintype "passive"))
      (node (ref "R15") (pin "2") (pinfunction "2_2") (pintype "passive"))
      (node (ref "R16") (pin "2") (pinfunction "2_2") (pintype "passive"))
      (node (ref "R2") (pin "1") (pinfunction "1_1") (pintype "passive"))
      (node (ref "R9") (pin "2") (pinfunction "2_2") (pintype "passive"))
      (node (ref "U10") (pin "6") (pinfunction "SEC_6") (pintype "passive"))
      (node (ref "U11") (pin "1") (pinfunction "GND_1") (pintype "passive"))
      (node (ref "U11") (pin "4") (pinfunction "GND_4") (pintype "passive"))
      (node (ref "U12") (pin "2") (pinfunction "GND_2") (pintype "passive"))
      (node (ref "U2") (pin "2") (pinfunction "GND_2") (pintype "passive"))
      (node (ref "U2") (pin "4") (pinfunction "GND_4") (pintype "passive"))
      (node (ref "U3") (pin "2") (pinfunction "GND_2") (pintype "passive"))
      (node (ref "U4") (pin "6") (pinfunction "SEC_6") (pintype "passive"))
      (node (ref "U5") (pin "2") (pinfunction "GND_2") (pintype "passive"))
      (node (ref "U6") (pin "2") (pinfunction "GND_2") (pintype "passive"))
      (node (ref "U6") (pin "3") (pinfunction "GND_3") (pintype "passive"))
      (node (ref "U6") (pin "5") (pinfunction "GND_5") (pintype "passive"))
      (node (ref "U7") (pin "2") (pinfunction "GND_2") (pintype "passive"))
      (node (ref "U8") (pin "0") (pinfunction "GND_0") (pintype "passive"))
      (node (ref "U9") (pin "2") (pinfunction "GND_2") (pintype "passive"))
      (node (ref "U9") (pin "3") (pinfunction "GND_3") (pintype "passive"))
      (node (ref "U9") (pin "5") (pinfunction "GND_5") (pintype "passive"))
    )
    (net (code "17") (name "Net-(C4-Pad2)") (class "Default")
      (node (ref "C4") (pin "2") (pinfunction "2_2") (pintype "passive"))
      (node (ref "R3") (pin "1") (pinfunction "1_1") (pintype "passive"))
    )
    (net (code "18") (name "Net-(C11-Pad2)") (class "Default")
      (node (ref "C11") (pin "2") (pinfunction "2_2") (pintype "passive"))
      (node (ref "C18") (pin "1") (pinfunction "1_1") (pintype "passive"))
      (node (ref "C19") (pin "1") (pinfunction "1_1") (pintype "passive"))
      (node (ref "R3") (pin "2") (pinfunction "2_2") (pintype "passive"))
    )
    (net (code "19") (name "Net-(C19-Pad2)") (class "Default")
      (node (ref "C19") (pin "2") (pinfunction "2_2") (pintype "passive"))
      (node (ref "R6") (pin "1") (pinfunction "1_1") (pintype "passive"))
    )
    (net (code "20") (name "Net-(C31-Pad2)") (class "Default")
      (node (ref "C31") (pin "2") (pinfunction "2_2") (pintype "passive"))
      (node (ref "R7") (pin "2") (pinfunction "2_2") (pintype "passive"))
    )
    (net (code "21") (name "Net-(C32-Pad2)") (class "Default")
      (node (ref "C32") (pin "2") (pinfunction "2_2") (pintype "passive"))
      (node (ref "R8") (pin "2") (pinfunction "2_2") (pintype "passive"))
    )
    (net (code "22") (name "Net-(C33-Pad1)") (class "Default")
      (node (ref "C33") (pin "1") (pinfunction "1_1") (pintype "passive"))
      (node (ref "L3") (pin "1") (pinfunction "1_1") (pintype "passive"))
      (node (ref "R5") (pin "2") (pinfunction "2_2") (pintype "passive"))
      (node (ref "R6") (pin "2") (pinfunction "2_2") (pintype "passive"))
    )
    (net (code "23") (name "Net-(C38-Pad1)") (class "Default")
      (node (ref "C38") (pin "1") (pinfunction "1_1") (pintype "passive"))
      (node (ref "R11") (pin "1") (pinfunction "1_1") (pintype "passive"))
      (node (ref "R13") (pin "2") (pinfunction "2_2") (pintype "passive"))
      (node (ref "R17") (pin "1") (pinfunction "1_1") (pintype "passive"))
    )
    (net (code "24") (name "Net-(C39-Pad1)") (class "Default")
      (node (ref "C39") (pin "1") (pinfunction "1_1") (pintype "passive"))
      (node (ref "R14") (pin "1") (pinfunction "1_1") (pintype "passive"))
      (node (ref "R15") (pin "1") (pinfunction "1_1") (pintype "passive"))
      (node (ref "R18") (pin "1") (pinfunction "1_1") (pintype "passive"))
    )
    (net (code "25") (name "Net-(C46-Pad2)") (class "Default")
      (node (ref "C46") (pin "2") (pinfunction "2_2") (pintype "passive"))
      (node (ref "R19") (pin "1") (pinfunction "1_1") (pintype "passive"))
    )
    (net (code "26") (name "Net-(C55-Pad2)") (class "Default")
      (node (ref "C55") (pin "2") (pinfunction "2_2") (pintype "passive"))
      (node (ref "R27") (pin "2") (pinfunction "2_2") (pintype "passive"))
    )
    (net (code "27") (name "Net-(C56-Pad2)") (class "Default")
      (node (ref "C56") (pin "2") (pinfunction "2_2") (pintype "passive"))
      (node (ref "R28") (pin "2") (pinfunction "2_2") (pintype "passive"))
    )
    (net (code "28") (name "Net-(D1-A)") (class "Default")
      (node (ref "D1") (pin "1") (pinfunction "A_1") (pintype "passive"))
      (node (ref "R10") (pin "1") (pinfunction "1_1") (pintype "passive"))
    )
    (net (code "29") (name "Net-(J1-Signal)") (class "Default")
      (node (ref "C3") (pin "1") (pinfunction "1_1") (pintype "passive"))
      (node (ref "C4") (pin "1") (pinfunction "1_1") (pintype "passive"))
      (node (ref "J1") (pin "1") (pinfunction "Signal_1") (pintype "input"))
      (node (ref "L1") (pin "2") (pinfunction "2_2") (pintype "passive"))
    )
    (net (code "30") (name "Net-(J2-Signal)") (class "Default")
      (node (ref "J2") (pin "1") (pinfunction "Signal_1") (pintype "input"))
      (node (ref "U4") (pin "4") (pinfunction "SEC-DOT_4") (pintype "passive"))
    )
    (net (code "31") (name "Net-(J3-Signal)") (class "Default")
      (node (ref "C38") (pin "2") (pinfunction "2_2") (pintype "passive"))
      (node (ref "J3") (pin "1") (pinfunction "Signal_1") (pintype "input"))
    )
    (net (code "32") (name "Net-(J4-Signal)") (class "Default")
      (node (ref "C39") (pin "2") (pinfunction "2_2") (pintype "passive"))
      (node (ref "J4") (pin "1") (pinfunction "Signal_1") (pintype "input"))
    )
    (net (code "33") (name "Net-(J5-Signal)") (class "Default")
      (node (ref "C50") (pin "2") (pinfunction "2_2") (pintype "passive"))
      (node (ref "J5") (pin "1") (pinfunction "Signal_1") (pintype "input"))
    )
    (net (code "34") (name "Net-(P2-Pad1)") (class "Default")
      (node (ref "P2") (pin "1") (pinfunction "1_1") (pintype "passive"))
      (node (ref "R20") (pin "1") (pinfunction "1_1") (pintype "passive"))
    )
    (net (code "35") (name "Net-(P2-Pad3)") (class "Default")
      (node (ref "P2") (pin "3") (pinfunction "3_3") (pintype "passive"))
      (node (ref "R21") (pin "1") (pinfunction "1_1") (pintype "passive"))
    )
    (net (code "36") (name "Net-(P2-Pad5)") (class "Default")
      (node (ref "P2") (pin "5") (pinfunction "5_5") (pintype "passive"))
      (node (ref "R22") (pin "1") (pinfunction "1_1") (pintype "passive"))
    )
    (net (code "37") (name "Net-(P2-Pad7)") (class "Default")
      (node (ref "P2") (pin "7") (pinfunction "7_7") (pintype "passive"))
      (node (ref "R24") (pin "1") (pinfunction "1_1") (pintype "passive"))
    )
    (net (code "38") (name "Net-(P2-Pad9)") (class "Default")
      (node (ref "P2") (pin "9") (pinfunction "9_9") (pintype "passive"))
      (node (ref "R25") (pin "1") (pinfunction "1_1") (pintype "passive"))
    )
    (net (code "39") (name "Net-(P2-Pad11)") (class "Default")
      (node (ref "P2") (pin "11") (pinfunction "11_11") (pintype "passive"))
      (node (ref "R26") (pin "1") (pinfunction "1_1") (pintype "passive"))
    )
    (net (code "40") (name "Net-(P2-Pad13)") (class "Default")
      (node (ref "P2") (pin "13") (pinfunction "13_13") (pintype "passive"))
      (node (ref "R29") (pin "1") (pinfunction "1_1") (pintype "passive"))
    )
    (net (code "41") (name "Net-(P2-Pad15)") (class "Default")
      (node (ref "P2") (pin "15") (pinfunction "15_15") (pintype "passive"))
      (node (ref "R30") (pin "1") (pinfunction "1_1") (pintype "passive"))
    )
    (net (code "42") (name "Net-(U1-ADJ)") (class "Default")
      (node (ref "R1") (pin "1") (pinfunction "1_1") (pintype "passive"))
      (node (ref "R2") (pin "2") (pinfunction "2_2") (pintype "passive"))
      (node (ref "U1") (pin "1") (pinfunction "ADJ_1") (pintype "passive"))
    )
    (net (code "43") (name "Net-(U2-RF_IN)") (class "Default")
      (node (ref "C3") (pin "2") (pinfunction "2_2") (pintype "passive"))
      (node (ref "U2") (pin "3") (pinfunction "RF_IN_3") (pintype "passive"))
    )
    (net (code "44") (name "Net-(U2-RF_OUT)") (class "Default")
      (node (ref "C11") (pin "1") (pinfunction "1_1") (pintype "passive"))
      (node (ref "L2") (pin "2") (pinfunction "2_2") (pintype "passive"))
      (node (ref "U2") (pin "1") (pinfunction "RF_OUT_1") (pintype "passive"))
    )
    (net (code "45") (name "Net-(U3-BP)") (class "Default")
      (node (ref "C16") (pin "1") (pinfunction "1_1") (pintype "passive"))
      (node (ref "C17") (pin "2") (pinfunction "2_2") (pintype "passive"))
      (node (ref "U3") (pin "4") (pinfunction "BP_4") (pintype "passive"))
    )
    (net (code "46") (name "Net-(U4-PRI)") (class "Default")
      (node (ref "R4") (pin "1") (pinfunction "1_1") (pintype "passive"))
      (node (ref "R7") (pin "1") (pinfunction "1_1") (pintype "passive"))
      (node (ref "U4") (pin "1") (pinfunction "PRI_1") (pintype "passive"))
    )
    (net (code "47") (name "Net-(U4-PRI-DOT)") (class "Default")
      (node (ref "R4") (pin "2") (pinfunction "2_2") (pintype "passive"))
      (node (ref "R8") (pin "1") (pinfunction "1_1") (pintype "passive"))
      (node (ref "U4") (pin "3") (pinfunction "PRI-DOT_3") (pintype "passive"))
    )
    (net (code "48") (name "Net-(U5-BP)") (class "Default")
      (node (ref "C24") (pin "1") (pinfunction "1_1") (pintype "passive"))
      (node (ref "C25") (pin "2") (pinfunction "2_2") (pintype "passive"))
      (node (ref "U5") (pin "4") (pinfunction "BP_4") (pintype "passive"))
    )
    (net (code "49") (name "Net-(U6-IN)") (class "Default")
      (node (ref "C18") (pin "2") (pinfunction "2_2") (pintype "passive"))
      (node (ref "U6") (pin "1") (pinfunction "IN_1") (pintype "passive"))
    )
    (net (code "50") (name "Net-(U6-OUT)") (class "Default")
      (node (ref "R5") (pin "1") (pinfunction "1_1") (pintype "passive"))
      (node (ref "U6") (pin "4") (pinfunction "OUT_4") (pintype "passive"))
    )
    (net (code "51") (name "Net-(U8-ANAINOUT)") (class "Default")
      (node (ref "C31") (pin "1") (pinfunction "1_1") (pintype "passive"))
      (node (ref "U8") (pin "16") (pinfunction "ANAINOUT_16") (pintype "passive"))
    )
    (net (code "52") (name "Net-(U8-ANAIPOUT)") (class "Default")
      (node (ref "C32") (pin "1") (pinfunction "1_1") (pintype "passive"))
      (node (ref "U8") (pin "15") (pinfunction "ANAIPOUT_15") (pintype "passive"))
    )
    (net (code "53") (name "Net-(U8-CPOUT)") (class "Default")
      (node (ref "C47") (pin "2") (pinfunction "2_2") (pintype "passive"))
      (node (ref "R19") (pin "2") (pinfunction "2_2") (pintype "passive"))
      (node (ref "U8") (pin "1") (pinfunction "CPOUT_1") (pintype "passive"))
    )
    (net (code "54") (name "Net-(U8-LD)") (class "Default")
      (node (ref "R10") (pin "2") (pinfunction "2_2") (pintype "passive"))
      (node (ref "U8") (pin "17") (pinfunction "LD_17") (pintype "passive"))
    )
    (net (code "55") (name "Net-(U8-LNAIN_HI)") (class "Default")
      (node (ref "L3") (pin "2") (pinfunction "2_2") (pintype "passive"))
      (node (ref "U8") (pin "19") (pinfunction "LNAIN_HI_19") (pintype "passive"))
    )
    (net (code "56") (name "Net-(U8-LNAIN_LO)") (class "Default")
      (node (ref "R9") (pin "1") (pinfunction "1_1") (pintype "passive"))
      (node (ref "U8") (pin "20") (pinfunction "LNAIN_LO_20") (pintype "passive"))
    )
    (net (code "57") (name "Net-(U8-LNAOUT_HI)") (class "Default")
      (node (ref "R12") (pin "1") (pinfunction "1_1") (pintype "passive"))
      (node (ref "R13") (pin "1") (pinfunction "1_1") (pintype "passive"))
      (node (ref "U8") (pin "24") (pinfunction "LNAOUT_HI_24") (pintype "passive"))
    )
    (net (code "58") (name "Net-(U8-MIXIN_HI)") (class "Default")
      (node (ref "R14") (pin "2") (pinfunction "2_2") (pintype "passive"))
      (node (ref "R16") (pin "1") (pinfunction "1_1") (pintype "passive"))
      (node (ref "U8") (pin "25") (pinfunction "MIXIN_HI_25") (pintype "passive"))
    )
    (net (code "59") (name "Net-(U8-XTAL)") (class "Default")
      (node (ref "C50") (pin "1") (pinfunction "1_1") (pintype "passive"))
      (node (ref "C52") (pin "2") (pinfunction "2_2") (pintype "passive"))
      (node (ref "C53") (pin "2") (pinfunction "2_2") (pintype "passive"))
      (node (ref "U8") (pin "3") (pinfunction "XTAL_3") (pintype "passive"))
    )
    (net (code "60") (name "Net-(U9-IN)") (class "Default")
      (node (ref "R17") (pin "2") (pinfunction "2_2") (pintype "passive"))
      (node (ref "U9") (pin "1") (pinfunction "IN_1") (pintype "passive"))
    )
    (net (code "61") (name "Net-(U9-OUT)") (class "Default")
      (node (ref "R18") (pin "2") (pinfunction "2_2") (pintype "passive"))
      (node (ref "U9") (pin "4") (pinfunction "OUT_4") (pintype "passive"))
    )
    (net (code "62") (name "Net-(U10-PRI)") (class "Default")
      (node (ref "R23") (pin "1") (pinfunction "1_1") (pintype "passive"))
      (node (ref "R27") (pin "1") (pinfunction "1_1") (pintype "passive"))
      (node (ref "U10") (pin "1") (pinfunction "PRI_1") (pintype "passive"))
    )
    (net (code "63") (name "Net-(U10-PRI-DOT)") (class "Default")
      (node (ref "R23") (pin "2") (pinfunction "2_2") (pintype "passive"))
      (node (ref "R28") (pin "1") (pinfunction "1_1") (pintype "passive"))
      (node (ref "U10") (pin "3") (pinfunction "PRI-DOT_3") (pintype "passive"))
    )
    (net (code "64") (name "Net-(U11-OUT)") (class "Default")
      (node (ref "C52") (pin "1") (pinfunction "1_1") (pintype "passive"))
      (node (ref "U11") (pin "5") (pinfunction "OUT_5") (pintype "passive"))
    )
    (net (code "65") (name "Net-(U12-Output)") (class "Default")
      (node (ref "C53") (pin "1") (pinfunction "1_1") (pintype "passive"))
      (node (ref "U12") (pin "3") (pinfunction "Output_3") (pintype "passive"))
    )
    (net (code "66") (name "Vin") (class "Default")
      (node (ref "C7") (pin "2") (pinfunction "2_2") (pintype "passive"))
      (node (ref "C8") (pin "2") (pinfunction "2_2") (pintype "passive"))
      (node (ref "U1") (pin "3") (pinfunction "IN_3") (pintype "passive"))
    )
    (net (code "67") (name "unconnected-(P2_2-Pad1)") (class "Default")
      (node (ref "P2_2") (pin "1") (pinfunction "1_1") (pintype "passive"))
    )
    (net (code "68") (name "unconnected-(P2_2-Pad2)") (class "Default")
      (node (ref "P2_2") (pin "2") (pinfunction "2_2") (pintype "passive"))
    )
    (net (code "69") (name "unconnected-(P2_2-Pad3)") (class "Default")
      (node (ref "P2_2") (pin "3") (pinfunction "3_3") (pintype "passive"))
    )
    (net (code "70") (name "unconnected-(P2_2-Pad4)") (class "Default")
      (node (ref "P2_2") (pin "4") (pinfunction "4_4") (pintype "passive"))
    )
    (net (code "71") (name "unconnected-(P2_2-Pad5)") (class "Default")
      (node (ref "P2_2") (pin "5") (pinfunction "5_5") (pintype "passive"))
    )
    (net (code "72") (name "unconnected-(P2_2-Pad6)") (class "Default")
      (node (ref "P2_2") (pin "6") (pinfunction "6_6") (pintype "passive"))
    )
    (net (code "73") (name "unconnected-(P2_2-Pad7)") (class "Default")
      (node (ref "P2_2") (pin "7") (pinfunction "7_7") (pintype "passive"))
    )
    (net (code "74") (name "unconnected-(P2_2-Pad8)") (class "Default")
      (node (ref "P2_2") (pin "8") (pinfunction "8_8") (pintype "passive"))
    )
    (net (code "75") (name "unconnected-(P2_2-Pad9)") (class "Default")
      (node (ref "P2_2") (pin "9") (pinfunction "9_9") (pintype "passive"))
    )
    (net (code "76") (name "unconnected-(P2_2-Pad10)") (class "Default")
      (node (ref "P2_2") (pin "10") (pinfunction "10_10") (pintype "passive"))
    )
    (net (code "77") (name "unconnected-(P2_2-Pad11)") (class "Default")
      (node (ref "P2_2") (pin "11") (pinfunction "11_11") (pintype "passive"))
    )
    (net (code "78") (name "unconnected-(U4-PRI-CT-Pad2)") (class "Default")
      (node (ref "U4") (pin "2") (pinfunction "PRI-CT_2") (pintype "passive"))
    )
    (net (code "79") (name "unconnected-(U4-SEC-CT-Pad5)") (class "Default")
      (node (ref "U4") (pin "5") (pinfunction "SEC-CT_5") (pintype "passive"))
    )
    (net (code "80") (name "unconnected-(U7-NC-Pad4)") (class "Default")
      (node (ref "U7") (pin "4") (pinfunction "NC_4") (pintype "passive"))
    )
    (net (code "81") (name "unconnected-(U8-LNAOUT_LO-Pad23)") (class "Default")
      (node (ref "U8") (pin "23") (pinfunction "LNAOUT_LO_23") (pintype "passive"))
    )
    (net (code "82") (name "unconnected-(U8-MIXIN_LO-Pad26)") (class "Default")
      (node (ref "U8") (pin "26") (pinfunction "MIXIN_LO_26") (pintype "passive"))
    )
    (net (code "83") (name "unconnected-(U8-NC-Pad21)") (class "Default")
      (node (ref "U8") (pin "21") (pinfunction "NC_21") (pintype "passive"))
    )
    (net (code "84") (name "unconnected-(U10-PRI-CT-Pad2)") (class "Default")
      (node (ref "U10") (pin "2") (pinfunction "PRI-CT_2") (pintype "passive"))
    )
    (net (code "85") (name "unconnected-(U10-SEC-CT-Pad5)") (class "Default")
      (node (ref "U10") (pin "5") (pinfunction "SEC-CT_5") (pintype "passive"))
    )
    (net (code "86") (name "unconnected-(U11-NC-Pad2)") (class "Default")
      (node (ref "U11") (pin "2") (pinfunction "NC_2") (pintype "passive"))
    )
    (net (code "87") (name "unconnected-(U11-NC-Pad3)") (class "Default")
      (node (ref "U11") (pin "3") (pinfunction "NC_3") (pintype "passive"))
    )
    (net (code "88") (name "unconnected-(U11-NC-Pad6)") (class "Default")
      (node (ref "U11") (pin "6") (pinfunction "NC_6") (pintype "passive"))
    )
    (net (code "89") (name "unconnected-(U11-NC-Pad7)") (class "Default")
      (node (ref "U11") (pin "7") (pinfunction "NC_7") (pintype "passive"))
    )
  )
)
